# PaxInstrument-T400D.net
KiCad netlist of a schematic drawn in EAGLE
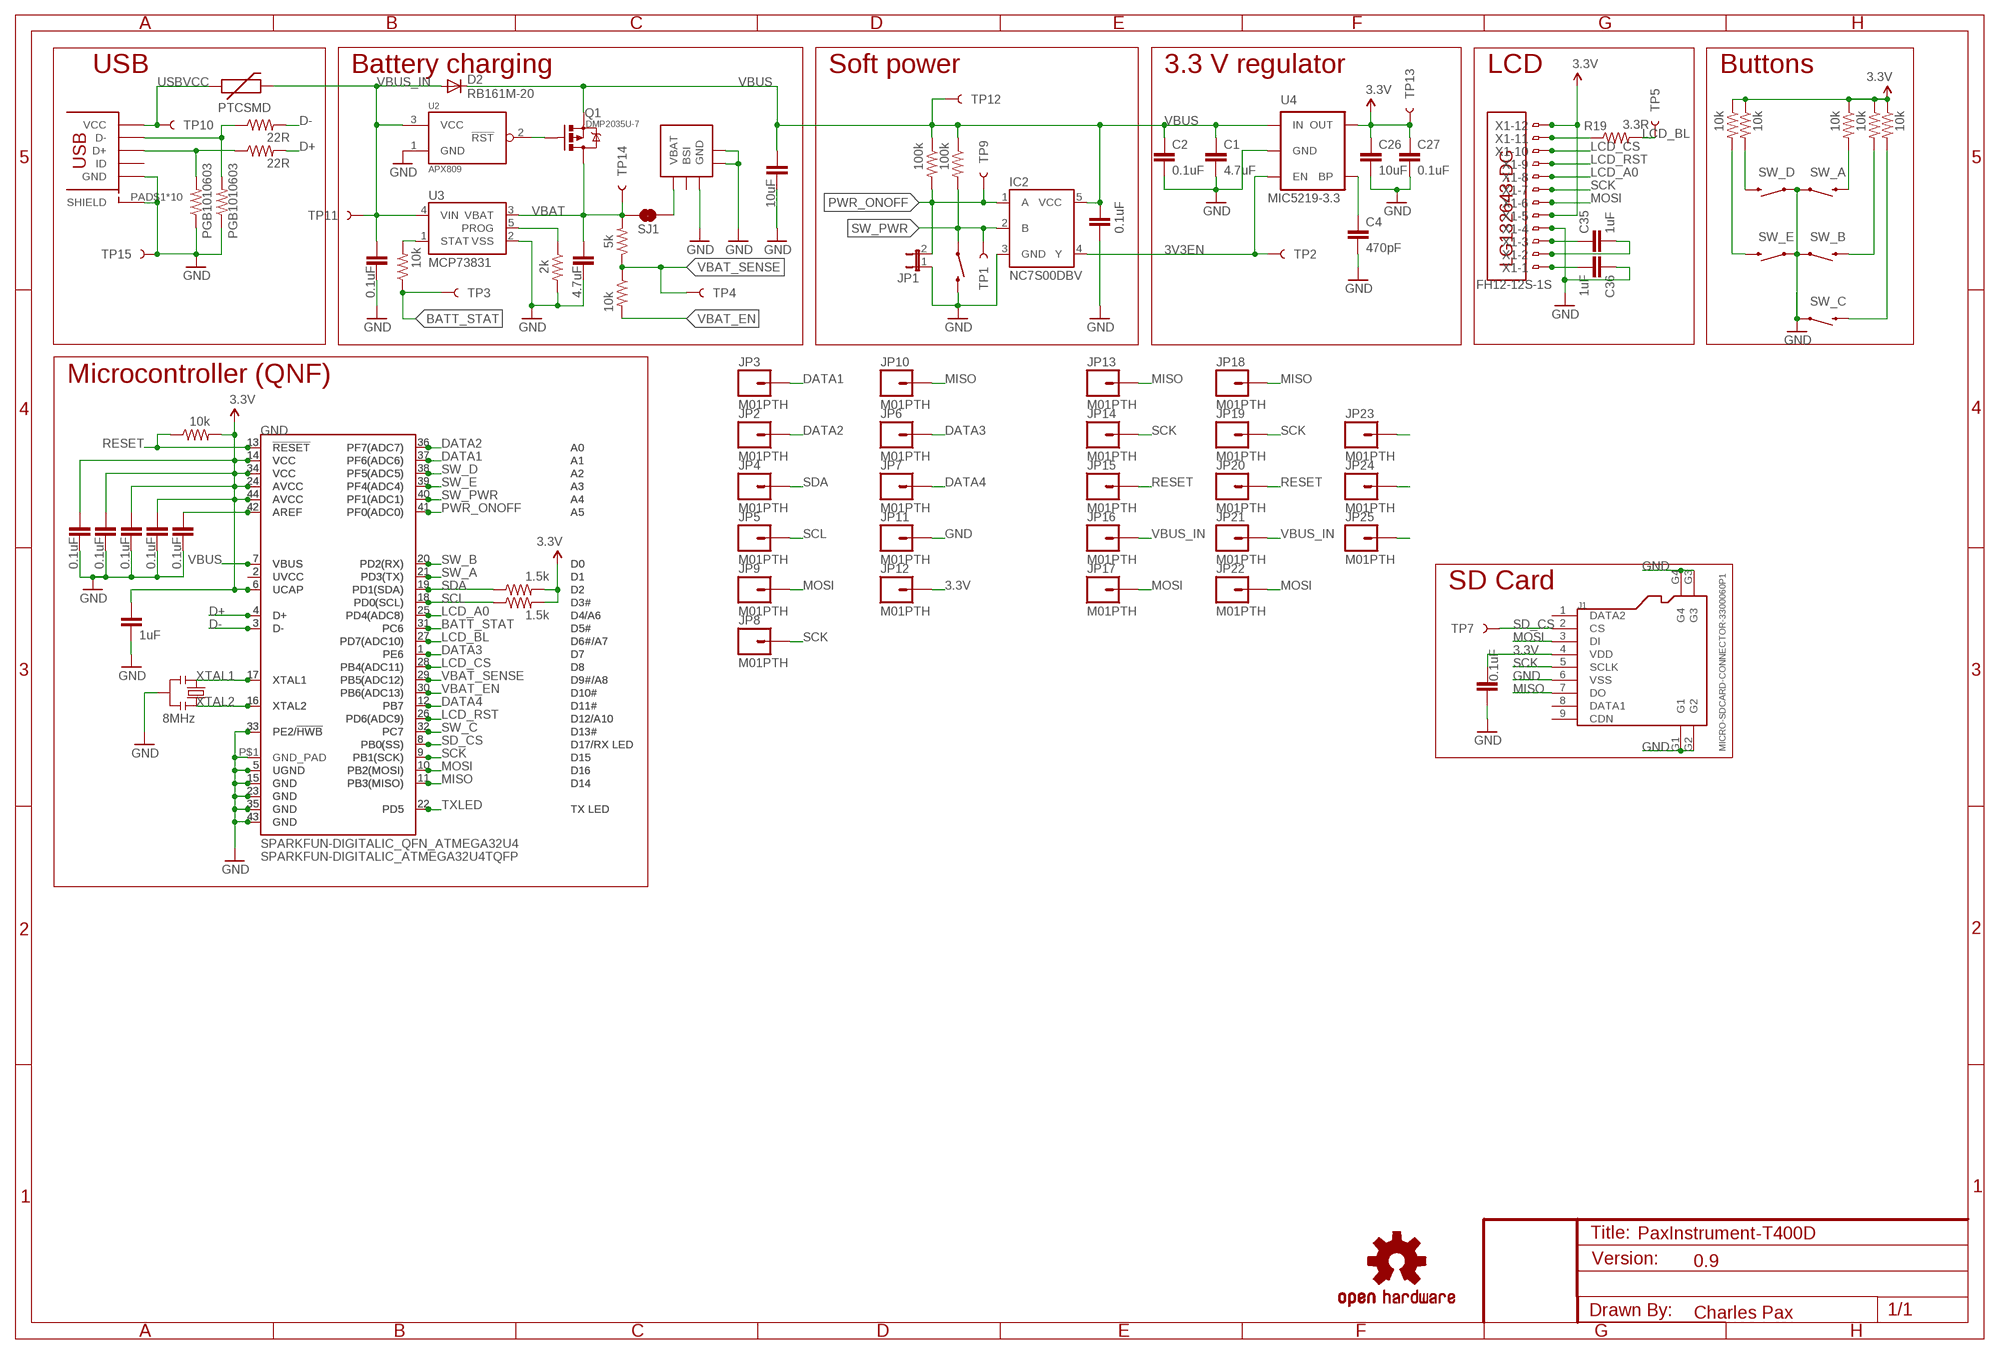
[diagram p0: schematic, sheet 1]

(export (version "E")
  (design (tool "Eeschema 10.0.6"))
  (components
    (comp (ref "C1")
      (value "4.7uF")
      (footprint "eagle-import:SPARKFUN-CAPACITORS_0603-CAP")
      (fields (field (name "MPN") "GRM188R60J475KE19D"))
      (libsource (lib "eagle-import") (part "SPARKFUN-CAPACITORS_CAP0603-CAP"))
    )
    (comp (ref "C2")
      (value "0.1uF")
      (footprint "eagle-import:SPARKFUN-CAPACITORS_0603-CAP")
      (fields (field (name "MPN") "CL10B104KO8NNNC"))
      (libsource (lib "eagle-import") (part "SPARKFUN-CAPACITORS_CAP0603-CAP"))
    )
    (comp (ref "C3")
      (value "0.1uF")
      (footprint "eagle-import:SPARKFUN-CAPACITORS_0603-CAP")
      (fields (field (name "MPN") "CL10B104KO8NNNC"))
      (libsource (lib "eagle-import") (part "SPARKFUN-CAPACITORS_CAP0603-CAP"))
    )
    (comp (ref "C4")
      (value "470pF")
      (footprint "eagle-import:SPARKFUN-CAPACITORS_0603-CAP")
      (fields (field (name "MPN") "C1608X5R1A474K080AA"))
      (libsource (lib "eagle-import") (part "SPARKFUN-CAPACITORS_CAP0603-CAP"))
    )
    (comp (ref "C5")
      (value "0.1uF")
      (footprint "eagle-import:SPARKFUN-CAPACITORS_0603-CAP")
      (fields (field (name "MPN") "CL10B104KO8NNNC"))
      (libsource (lib "eagle-import") (part "SPARKFUN-CAPACITORS_CAP0603-CAP"))
    )
    (comp (ref "C6")
      (value "0.1uF")
      (footprint "eagle-import:SPARKFUN-CAPACITORS_0603-CAP")
      (fields (field (name "MPN") "CL10B104KO8NNNC"))
      (libsource (lib "eagle-import") (part "SPARKFUN-CAPACITORS_CAP0603-CAP"))
    )
    (comp (ref "C9")
      (value "4.7uF")
      (footprint "eagle-import:SPARKFUN-CAPACITORS_0603-CAP")
      (fields (field (name "MPN") "GRM188R60J475KE19D"))
      (libsource (lib "eagle-import") (part "SPARKFUN-CAPACITORS_CAP0603-CAP"))
    )
    (comp (ref "C12")
      (value "10uF")
      (footprint "eagle-import:SPARKFUN-CAPACITORS_0603-CAP")
      (fields (field (name "MPN") "JMK107ABJ106MAHT"))
      (libsource (lib "eagle-import") (part "SPARKFUN-CAPACITORS_CAP0603-CAP"))
    )
    (comp (ref "C19")
      (value "1uF")
      (footprint "eagle-import:SPARKFUN-CAPACITORS_0603-CAP")
      (fields (field (name "MPN") "LMK107B7105KA-T"))
      (libsource (lib "eagle-import") (part "SPARKFUN-CAPACITORS_CAP0603-CAP"))
    )
    (comp (ref "C21")
      (value "0.1uF")
      (footprint "eagle-import:SPARKFUN-CAPACITORS_0603-CAP")
      (fields (field (name "MPN") "CL10B104KO8NNNC"))
      (libsource (lib "eagle-import") (part "SPARKFUN-CAPACITORS_CAP0603-CAP"))
    )
    (comp (ref "C26")
      (value "10uF")
      (footprint "eagle-import:SPARKFUN-CAPACITORS_0603-CAP")
      (fields (field (name "MPN") "JMK107ABJ106MAHT"))
      (libsource (lib "eagle-import") (part "SPARKFUN-CAPACITORS_CAP0603-CAP"))
    )
    (comp (ref "C27")
      (value "0.1uF")
      (footprint "eagle-import:SPARKFUN-CAPACITORS_0603-CAP")
      (fields (field (name "MPN") "CL10B104KO8NNNC"))
      (libsource (lib "eagle-import") (part "SPARKFUN-CAPACITORS_CAP0603-CAP"))
    )
    (comp (ref "C28")
      (value "0.1uF")
      (footprint "eagle-import:SPARKFUN-CAPACITORS_0603-CAP")
      (fields (field (name "MPN") "CL10B104KO8NNNC"))
      (libsource (lib "eagle-import") (part "SPARKFUN-CAPACITORS_CAP0603-CAP"))
    )
    (comp (ref "C32")
      (value "0.1uF")
      (footprint "eagle-import:SPARKFUN-CAPACITORS_0603-CAP")
      (fields (field (name "MPN") "CL10B104KO8NNNC"))
      (libsource (lib "eagle-import") (part "SPARKFUN-CAPACITORS_CAP0603-CAP"))
    )
    (comp (ref "C33")
      (value "0.1uF")
      (footprint "eagle-import:SPARKFUN-CAPACITORS_0603-CAP")
      (fields (field (name "MPN") "CL10B104KO8NNNC"))
      (libsource (lib "eagle-import") (part "SPARKFUN-CAPACITORS_CAP0603-CAP"))
    )
    (comp (ref "C34")
      (value "0.1uF")
      (footprint "eagle-import:SPARKFUN-CAPACITORS_0603-CAP")
      (fields (field (name "MPN") "CL10B104KO8NNNC"))
      (libsource (lib "eagle-import") (part "SPARKFUN-CAPACITORS_CAP0603-CAP"))
    )
    (comp (ref "C35")
      (value "1uF")
      (footprint "eagle-import:SPARKFUN-CAPACITORS_0603-CAP")
      (fields (field (name "MPN") "LMK107B7105KA-T"))
      (libsource (lib "eagle-import") (part "SPARKFUN-CAPACITORS_CAP0603-CAP"))
    )
    (comp (ref "C36")
      (value "1uF")
      (footprint "eagle-import:SPARKFUN-CAPACITORS_0603-CAP")
      (fields (field (name "MPN") "LMK107B7105KA-T"))
      (libsource (lib "eagle-import") (part "SPARKFUN-CAPACITORS_CAP0603-CAP"))
    )
    (comp (ref "D2")
      (value "RB161M-20")
      (footprint "eagle-import:SOD123")
      (fields (field (name "MPN") "B340A-13-F"))
      (libsource (lib "eagle-import") (part "SPARKFUN-DISCRETESEMI_DIODESOD123SOD123"))
    )
    (comp (ref "F1")
      (value "PTCSMD")
      (footprint "eagle-import:PTC-1206")
      (fields (field (name "MPN") "MF-NSMF050-2"))
      (libsource (lib "eagle-import") (part "PTCSMD"))
    )
    (comp (ref "GND")
      (value "SPARKFUN-DIGITALIC_QFN_ATMEGA32U4")
      (footprint "eagle-import:SPARKFUN-DIGITALIC_SPARKFUN-DIGITALIC_QFN-44")
      (libsource (lib "eagle-import") (part "SPARKFUN-DIGITALIC_QFN_ATMEGA32U4"))
    )
    (comp (ref "IC2")
      (value "NC7S00DBV")
      (footprint "eagle-import:CHARLESPAX_SOT23-5")
      (libsource (lib "eagle-import") (part "NC7S00DBV"))
    )
    (comp (ref "J1")
      (value "MICRO-SDCARD-CONNECTOR-3300060P1")
      (footprint "eagle-import:9P-SMD-W-RING")
      (libsource (lib "eagle-import") (part "MICRO-SDCARD-CONNECTOR-3300060P1"))
    )
    (comp (ref "JP1")
      (value "JUMPER-2SMD-NO")
      (footprint "eagle-import:SJ_2S-NO")
      (libsource (lib "eagle-import") (part "JUMPER-2SMD-NO"))
    )
    (comp (ref "JP2")
      (value "M01PTH")
      (footprint "eagle-import:1X01")
      (libsource (lib "eagle-import") (part "M01PTH"))
    )
    (comp (ref "JP3")
      (value "M01PTH")
      (footprint "eagle-import:1X01")
      (libsource (lib "eagle-import") (part "M01PTH"))
    )
    (comp (ref "JP4")
      (value "M01PTH")
      (footprint "eagle-import:1X01")
      (libsource (lib "eagle-import") (part "M01PTH"))
    )
    (comp (ref "JP5")
      (value "M01PTH")
      (footprint "eagle-import:1X01")
      (libsource (lib "eagle-import") (part "M01PTH"))
    )
    (comp (ref "JP6")
      (value "M01PTH")
      (footprint "eagle-import:1X01")
      (libsource (lib "eagle-import") (part "M01PTH"))
    )
    (comp (ref "JP7")
      (value "M01PTH")
      (footprint "eagle-import:1X01")
      (libsource (lib "eagle-import") (part "M01PTH"))
    )
    (comp (ref "JP8")
      (value "M01PTH")
      (footprint "eagle-import:1X01")
      (libsource (lib "eagle-import") (part "M01PTH"))
    )
    (comp (ref "JP9")
      (value "M01PTH")
      (footprint "eagle-import:1X01")
      (libsource (lib "eagle-import") (part "M01PTH"))
    )
    (comp (ref "JP10")
      (value "M01PTH")
      (footprint "eagle-import:1X01")
      (libsource (lib "eagle-import") (part "M01PTH"))
    )
    (comp (ref "JP11")
      (value "M01PTH")
      (footprint "eagle-import:1X01")
      (libsource (lib "eagle-import") (part "M01PTH"))
    )
    (comp (ref "JP12")
      (value "M01PTH")
      (footprint "eagle-import:1X01")
      (libsource (lib "eagle-import") (part "M01PTH"))
    )
    (comp (ref "JP13")
      (value "M01PTH")
      (footprint "eagle-import:1X01")
      (libsource (lib "eagle-import") (part "M01PTH"))
    )
    (comp (ref "JP14")
      (value "M01PTH")
      (footprint "eagle-import:1X01")
      (libsource (lib "eagle-import") (part "M01PTH"))
    )
    (comp (ref "JP15")
      (value "M01PTH")
      (footprint "eagle-import:1X01")
      (libsource (lib "eagle-import") (part "M01PTH"))
    )
    (comp (ref "JP16")
      (value "M01PTH")
      (footprint "eagle-import:1X01")
      (libsource (lib "eagle-import") (part "M01PTH"))
    )
    (comp (ref "JP17")
      (value "M01PTH")
      (footprint "eagle-import:1X01")
      (libsource (lib "eagle-import") (part "M01PTH"))
    )
    (comp (ref "JP18")
      (value "M01PTH")
      (footprint "eagle-import:1X01")
      (libsource (lib "eagle-import") (part "M01PTH"))
    )
    (comp (ref "JP19")
      (value "M01PTH")
      (footprint "eagle-import:1X01")
      (libsource (lib "eagle-import") (part "M01PTH"))
    )
    (comp (ref "JP20")
      (value "M01PTH")
      (footprint "eagle-import:1X01")
      (libsource (lib "eagle-import") (part "M01PTH"))
    )
    (comp (ref "JP21")
      (value "M01PTH")
      (footprint "eagle-import:1X01")
      (libsource (lib "eagle-import") (part "M01PTH"))
    )
    (comp (ref "JP22")
      (value "M01PTH")
      (footprint "eagle-import:1X01")
      (libsource (lib "eagle-import") (part "M01PTH"))
    )
    (comp (ref "JP23")
      (value "M01PTH")
      (footprint "eagle-import:1X01")
      (libsource (lib "eagle-import") (part "M01PTH"))
    )
    (comp (ref "JP24")
      (value "M01PTH")
      (footprint "eagle-import:1X01")
      (libsource (lib "eagle-import") (part "M01PTH"))
    )
    (comp (ref "JP25")
      (value "M01PTH")
      (footprint "eagle-import:1X01")
      (libsource (lib "eagle-import") (part "M01PTH"))
    )
    (comp (ref "LOGO1")
      (value "OSHW-LOGOS")
      (footprint "eagle-import:OSHW-LOGO-S")
      (libsource (lib "eagle-import") (part "OSHW-LOGOS"))
    )
    (comp (ref "Q1")
      (value "DMP2035U-7")
      (footprint "eagle-import:SOT23")
      (libsource (lib "eagle-import") (part "MOSFET-PCHANNELSMT"))
    )
    (comp (ref "R3")
      (value "2k")
      (footprint "eagle-import:SPARKFUN-RESISTORS_0603-RES")
      (fields (field (name "MPN") "ESR03EZPJ202"))
      (libsource (lib "eagle-import") (part "SPARKFUN-RESISTORS_RESISTOR0603-RES"))
    )
    (comp (ref "R4")
      (value "10k")
      (footprint "eagle-import:SPARKFUN-RESISTORS_0603-RES")
      (fields (field (name "MPN") "RC1608J103CS"))
      (libsource (lib "eagle-import") (part "SPARKFUN-RESISTORS_RESISTOR0603-RES"))
    )
    (comp (ref "R6")
      (value "100k")
      (footprint "eagle-import:SPARKFUN-RESISTORS_0603-RES")
      (fields (field (name "MPN") "RC1608J103CS"))
      (libsource (lib "eagle-import") (part "SPARKFUN-RESISTORS_RESISTOR0603-RES"))
    )
    (comp (ref "R7")
      (value "100k")
      (footprint "eagle-import:SPARKFUN-RESISTORS_0603-RES")
      (fields (field (name "MPN") "RC1608J103CS"))
      (libsource (lib "eagle-import") (part "SPARKFUN-RESISTORS_RESISTOR0603-RES"))
    )
    (comp (ref "R8")
      (value "10k")
      (footprint "eagle-import:SPARKFUN-RESISTORS_0603-RES")
      (fields (field (name "MPN") "RC1608J103CS"))
      (libsource (lib "eagle-import") (part "SPARKFUN-RESISTORS_RESISTOR0603-RES"))
    )
    (comp (ref "R9")
      (value "22R")
      (footprint "eagle-import:SPARKFUN-RESISTORS_0603-RES")
      (fields (field (name "MPN") "RC0603JR-0722RL"))
      (libsource (lib "eagle-import") (part "SPARKFUN-RESISTORS_RESISTOR0603-RES"))
    )
    (comp (ref "R10")
      (value "22R")
      (footprint "eagle-import:SPARKFUN-RESISTORS_0603-RES")
      (fields (field (name "MPN") "RC0603JR-0722RL"))
      (libsource (lib "eagle-import") (part "SPARKFUN-RESISTORS_RESISTOR0603-RES"))
    )
    (comp (ref "R11")
      (value "10k")
      (footprint "eagle-import:SPARKFUN-RESISTORS_0603-RES")
      (fields (field (name "MPN") "RC1608J103CS"))
      (libsource (lib "eagle-import") (part "SPARKFUN-RESISTORS_RESISTOR0603-RES"))
    )
    (comp (ref "R12")
      (value "10k")
      (footprint "eagle-import:SPARKFUN-RESISTORS_0603-RES")
      (fields (field (name "MPN") "RC1608J103CS"))
      (libsource (lib "eagle-import") (part "SPARKFUN-RESISTORS_RESISTOR0603-RES"))
    )
    (comp (ref "R13")
      (value "1.5k")
      (footprint "eagle-import:SPARKFUN-RESISTORS_0603-RES")
      (fields (field (name "MPN") "RC0603JR-071K5L"))
      (libsource (lib "eagle-import") (part "SPARKFUN-RESISTORS_RESISTOR0603-RES"))
    )
    (comp (ref "R14")
      (value "1.5k")
      (footprint "eagle-import:SPARKFUN-RESISTORS_0603-RES")
      (fields (field (name "MPN") "RC0603JR-071K5L"))
      (libsource (lib "eagle-import") (part "SPARKFUN-RESISTORS_RESISTOR0603-RES"))
    )
    (comp (ref "R15")
      (value "10k")
      (footprint "eagle-import:SPARKFUN-RESISTORS_0603-RES")
      (fields (field (name "MPN") "RC1608J103CS"))
      (libsource (lib "eagle-import") (part "SPARKFUN-RESISTORS_RESISTOR0603-RES"))
    )
    (comp (ref "R16")
      (value "10k")
      (footprint "eagle-import:SPARKFUN-RESISTORS_0603-RES")
      (fields (field (name "MPN") "RC1608J103CS"))
      (libsource (lib "eagle-import") (part "SPARKFUN-RESISTORS_RESISTOR0603-RES"))
    )
    (comp (ref "R17")
      (value "10k")
      (footprint "eagle-import:SPARKFUN-RESISTORS_0603-RES")
      (fields (field (name "MPN") "RC1608J103CS"))
      (libsource (lib "eagle-import") (part "SPARKFUN-RESISTORS_RESISTOR0603-RES"))
    )
    (comp (ref "R19")
      (value "3.3R")
      (footprint "eagle-import:SPARKFUN-RESISTORS_0603-RES")
      (libsource (lib "eagle-import") (part "SPARKFUN-RESISTORS_RESISTOR0603-RES"))
    )
    (comp (ref "R20")
      (value "5k")
      (footprint "eagle-import:SPARKFUN-RESISTORS_0603-RES")
      (fields (field (name "MPN") "RC1608J103CS"))
      (libsource (lib "eagle-import") (part "SPARKFUN-RESISTORS_RESISTOR0603-RES"))
    )
    (comp (ref "R24")
      (value "10k")
      (footprint "eagle-import:SPARKFUN-RESISTORS_0603-RES")
      (fields (field (name "MPN") "RC1608J103CS"))
      (libsource (lib "eagle-import") (part "SPARKFUN-RESISTORS_RESISTOR0603-RES"))
    )
    (comp (ref "S1")
      (value "SWITCH-MOMENTARY-2SMD")
      (footprint "eagle-import:TACTILE_SWITCH_SMD")
      (libsource (lib "eagle-import") (part "SWITCH-MOMENTARY-2SMD"))
    )
    (comp (ref "S2")
      (value "SWITCH-MOMENTARY-2SMD")
      (footprint "eagle-import:TACTILE_SWITCH_SMD")
      (libsource (lib "eagle-import") (part "SWITCH-MOMENTARY-2SMD"))
    )
    (comp (ref "S3")
      (value "SWITCH-MOMENTARY-2SMD")
      (footprint "eagle-import:TACTILE_SWITCH_SMD")
      (libsource (lib "eagle-import") (part "SWITCH-MOMENTARY-2SMD"))
    )
    (comp (ref "S4")
      (value "SWITCH-MOMENTARY-2SMD")
      (footprint "eagle-import:TACTILE_SWITCH_SMD")
      (libsource (lib "eagle-import") (part "SWITCH-MOMENTARY-2SMD"))
    )
    (comp (ref "S5")
      (value "SWITCH-MOMENTARY-2SMD")
      (footprint "eagle-import:TACTILE_SWITCH_SMD")
      (libsource (lib "eagle-import") (part "SWITCH-MOMENTARY-2SMD"))
    )
    (comp (ref "S6")
      (value "SWITCH-MOMENTARY-2SMD")
      (footprint "eagle-import:TACTILE_SWITCH_SMD")
      (libsource (lib "eagle-import") (part "SWITCH-MOMENTARY-2SMD"))
    )
    (comp (ref "SJ1")
      (value "JUMPER-PAD-2-NC_BY_TRACE")
      (footprint "eagle-import:PAD-JUMPER-2-NC_BY_TRACE_YES_SILK")
      (libsource (lib "eagle-import") (part "JUMPER-PAD-2-NC_BY_TRACE"))
    )
    (comp (ref "TP1")
      (value "SW_PWR")
      (footprint "eagle-import:TP_15TH")
      (libsource (lib "eagle-import") (part "TEST-POINTTP_15TH_THRU"))
    )
    (comp (ref "TP2")
      (value "3V3_EN")
      (footprint "eagle-import:TP_15TH")
      (libsource (lib "eagle-import") (part "TEST-POINTTP_15TH_THRU"))
    )
    (comp (ref "TP3")
      (value "BATT_STAT")
      (footprint "eagle-import:TP_15TH")
      (libsource (lib "eagle-import") (part "TEST-POINTTP_15TH_THRU"))
    )
    (comp (ref "TP4")
      (value "VBAT_SENSE")
      (footprint "eagle-import:TP_15TH")
      (libsource (lib "eagle-import") (part "TEST-POINTTP_15TH_THRU"))
    )
    (comp (ref "TP5")
      (value "LCD_BL")
      (footprint "eagle-import:TP_15TH")
      (libsource (lib "eagle-import") (part "TEST-POINTTP_15TH_THRU"))
    )
    (comp (ref "TP7")
      (value "SD_CS")
      (footprint "eagle-import:TP_15TH")
      (libsource (lib "eagle-import") (part "TEST-POINTTP_15TH_THRU"))
    )
    (comp (ref "TP9")
      (value "PWR_ON/OFF")
      (footprint "eagle-import:TP_15TH")
      (libsource (lib "eagle-import") (part "TEST-POINTTP_15TH_THRU"))
    )
    (comp (ref "TP10")
      (value "TEST-POINTTP_15TH_THRU")
      (footprint "eagle-import:TP_15TH")
      (libsource (lib "eagle-import") (part "TEST-POINTTP_15TH_THRU"))
    )
    (comp (ref "TP11")
      (value "VBUS_IN")
      (footprint "eagle-import:TP_15TH")
      (libsource (lib "eagle-import") (part "TEST-POINTTP_15TH_THRU"))
    )
    (comp (ref "TP12")
      (value "VBUS")
      (footprint "eagle-import:TP_15TH")
      (libsource (lib "eagle-import") (part "TEST-POINTTP_15TH_THRU"))
    )
    (comp (ref "TP13")
      (value "3.3V")
      (footprint "eagle-import:TP_15TH")
      (libsource (lib "eagle-import") (part "TEST-POINTTP_15TH_THRU"))
    )
    (comp (ref "TP14")
      (value "VBAT")
      (footprint "eagle-import:TP_15TH")
      (libsource (lib "eagle-import") (part "TEST-POINTTP_15TH_THRU"))
    )
    (comp (ref "TP15")
      (value "GND")
      (footprint "eagle-import:TP_15TH")
      (libsource (lib "eagle-import") (part "TEST-POINTTP_15TH_THRU"))
    )
    (comp (ref "U$1")
      (value "USB_MICROSMT+THRUHULE")
      (footprint "eagle-import:USB_MICRO_THRUHOLE")
      (fields (field (name "MPN") "10118194-0001LF"))
      (libsource (lib "eagle-import") (part "USB_MICROSMT+THRUHULE"))
    )
    (comp (ref "U$2")
      (value "BL-5C-CONNECTOR")
      (footprint "eagle-import:BL-5C-CONNECTOR")
      (libsource (lib "eagle-import") (part "BL-5C-CONNECTOR"))
    )
    (comp (ref "U$3")
      (value "SPARKFUN-DIGITALIC_ATMEGA32U4TQFP")
      (footprint "eagle-import:SPARKFUN-DIGITALIC_SPARKFUN-DIGITALIC_TQFP44")
      (libsource (lib "eagle-import") (part "SPARKFUN-DIGITALIC_ATMEGA32U4TQFP"))
    )
    (comp (ref "U$5")
      (value "LG132643-DG")
      (footprint "eagle-import:LG132643-DG")
      (fields (field (name "MPN") "LG132643-DW"))
      (libsource (lib "eagle-import") (part "LG132643-DG"))
    )
    (comp (ref "U2")
      (value "APX809")
      (footprint "eagle-import:SOT23")
      (libsource (lib "eagle-import") (part "APX809"))
    )
    (comp (ref "U3")
      (value "MCP73831")
      (footprint "eagle-import:SOT23-5")
      (fields (field (name "MPN") "MCP73831T-2DCI/OT"))
      (libsource (lib "eagle-import") (part "MCP73831"))
    )
    (comp (ref "U4")
      (value "MIC5219-3.3V")
      (footprint "eagle-import:SOT23-5")
      (fields (field (name "MPN") "MIC5219-3.3YM5 TR"))
      (libsource (lib "eagle-import") (part "V_REG_LDOSMD"))
    )
    (comp (ref "X1")
      (value "FH12-12S-1S")
      (footprint "eagle-import:FH12-12S-1SH")
      (libsource (lib "eagle-import") (part "FH12-12S-1S"))
    )
    (comp (ref "X2")
      (value "FH12-12S-0.5SH")
      (footprint "eagle-import:FH12-12S-0.5SH")
      (fields (field (name "MPN") "FH12-12S-0.5SH(55)"))
      (libsource (lib "eagle-import") (part "FH12-12S-0.5SH"))
    )
    (comp (ref "Y1")
      (value "RESONATORSMD")
      (footprint "eagle-import:RESONATOR-SMD")
      (fields (field (name "MPN") "CSTCE8M00G52-R0"))
      (libsource (lib "eagle-import") (part "RESONATORSMD"))
    )
    (comp (ref "Z1")
      (value "PGB1010603")
      (footprint "eagle-import:SPARKFUN-RESISTORS_0603-RES")
      (fields (field (name "MPN") "PGB1010603NRHF"))
      (libsource (lib "eagle-import") (part "SPARKFUN-RESISTORS_RESISTOR0603-RES"))
    )
    (comp (ref "Z2")
      (value "PGB1010603")
      (footprint "eagle-import:SPARKFUN-RESISTORS_0603-RES")
      (fields (field (name "MPN") "PGB1010603NRHF"))
      (libsource (lib "eagle-import") (part "SPARKFUN-RESISTORS_RESISTOR0603-RES"))
    )
  )
  (nets
    (net (code "1") (name "/3V3EN") (class "Default")
      (node (ref "IC2") (pin "4") (pinfunction "Y_4") (pintype "output"))
      (node (ref "TP2") (pin "P$1") (pinfunction "1_P$1") (pintype "bidirectional"))
      (node (ref "U4") (pin "3") (pinfunction "EN_3") (pintype "input"))
    )
    (net (code "2") (name "/D+") (class "Default")
      (node (ref "GND") (pin "4") (pinfunction "D+_4") (pintype "bidirectional"))
      (node (ref "R9") (pin "2") (pinfunction "2_2") (pintype "passive"))
      (node (ref "U$3") (pin "4") (pinfunction "D+_4") (pintype "bidirectional"))
    )
    (net (code "3") (name "/D-") (class "Default")
      (node (ref "GND") (pin "3") (pinfunction "D-_3") (pintype "bidirectional"))
      (node (ref "R10") (pin "2") (pinfunction "2_2") (pintype "passive"))
      (node (ref "U$3") (pin "3") (pinfunction "D-_3") (pintype "bidirectional"))
    )
    (net (code "4") (name "/DATA1") (class "Default")
      (node (ref "GND") (pin "37") (pinfunction "PF6(ADC6)_37") (pintype "bidirectional"))
      (node (ref "JP3") (pin "1") (pinfunction "1_1") (pintype "passive"))
      (node (ref "U$3") (pin "37") (pinfunction "PF6(ADC6)_37") (pintype "bidirectional"))
    )
    (net (code "5") (name "/DATA2") (class "Default")
      (node (ref "GND") (pin "36") (pinfunction "PF7(ADC7)_36") (pintype "bidirectional"))
      (node (ref "JP2") (pin "1") (pinfunction "1_1") (pintype "passive"))
      (node (ref "U$3") (pin "36") (pinfunction "PF7(ADC7)_36") (pintype "bidirectional"))
    )
    (net (code "6") (name "/DATA3") (class "Default")
      (node (ref "GND") (pin "1") (pinfunction "PE6_1") (pintype "bidirectional"))
      (node (ref "JP6") (pin "1") (pinfunction "1_1") (pintype "passive"))
      (node (ref "U$3") (pin "1") (pinfunction "PE6_1") (pintype "bidirectional"))
    )
    (net (code "7") (name "/DATA4") (class "Default")
      (node (ref "GND") (pin "12") (pinfunction "PB7_12") (pintype "bidirectional"))
      (node (ref "JP7") (pin "1") (pinfunction "1_1") (pintype "passive"))
      (node (ref "U$3") (pin "12") (pinfunction "PB7_12") (pintype "bidirectional"))
    )
    (net (code "8") (name "/LCD_A0") (class "Default")
      (node (ref "GND") (pin "25") (pinfunction "PD4(ADC8)_25") (pintype "bidirectional"))
      (node (ref "U$3") (pin "25") (pinfunction "PD4(ADC8)_25") (pintype "bidirectional"))
      (node (ref "X1") (pin "8") (pinfunction "1_8") (pintype "passive"))
      (node (ref "X2") (pin "8") (pinfunction "1_8") (pintype "passive"))
    )
    (net (code "9") (name "/LCD_BL") (class "Default")
      (node (ref "GND") (pin "27") (pinfunction "PD7(ADC10)_27") (pintype "bidirectional"))
      (node (ref "R19") (pin "2") (pinfunction "2_2") (pintype "passive"))
      (node (ref "TP5") (pin "P$1") (pinfunction "1_P$1") (pintype "bidirectional"))
      (node (ref "U$3") (pin "27") (pinfunction "PD7(ADC10)_27") (pintype "bidirectional"))
    )
    (net (code "10") (name "/LCD_CS") (class "Default")
      (node (ref "GND") (pin "28") (pinfunction "PB4(ADC11)_28") (pintype "bidirectional"))
      (node (ref "U$3") (pin "28") (pinfunction "PB4(ADC11)_28") (pintype "bidirectional"))
      (node (ref "X1") (pin "10") (pinfunction "1_10") (pintype "passive"))
      (node (ref "X2") (pin "10") (pinfunction "1_10") (pintype "passive"))
    )
    (net (code "11") (name "/LCD_RST") (class "Default")
      (node (ref "GND") (pin "26") (pinfunction "PD6(ADC9)_26") (pintype "bidirectional"))
      (node (ref "U$3") (pin "26") (pinfunction "PD6(ADC9)_26") (pintype "bidirectional"))
      (node (ref "X1") (pin "9") (pinfunction "1_9") (pintype "passive"))
      (node (ref "X2") (pin "9") (pinfunction "1_9") (pintype "passive"))
    )
    (net (code "12") (name "/MISO") (class "Default")
      (node (ref "GND") (pin "11") (pinfunction "PB3(MISO)_11") (pintype "bidirectional"))
      (node (ref "J1") (pin "7") (pinfunction "DO_7") (pintype "bidirectional"))
      (node (ref "JP10") (pin "1") (pinfunction "1_1") (pintype "passive"))
      (node (ref "JP13") (pin "1") (pinfunction "1_1") (pintype "passive"))
      (node (ref "JP18") (pin "1") (pinfunction "1_1") (pintype "passive"))
      (node (ref "U$3") (pin "11") (pinfunction "PB3(MISO)_11") (pintype "bidirectional"))
    )
    (net (code "13") (name "/MOSI") (class "Default")
      (node (ref "GND") (pin "10") (pinfunction "PB2(MOSI)_10") (pintype "bidirectional"))
      (node (ref "J1") (pin "3") (pinfunction "DI_3") (pintype "bidirectional"))
      (node (ref "JP17") (pin "1") (pinfunction "1_1") (pintype "passive"))
      (node (ref "JP22") (pin "1") (pinfunction "1_1") (pintype "passive"))
      (node (ref "JP9") (pin "1") (pinfunction "1_1") (pintype "passive"))
      (node (ref "U$3") (pin "10") (pinfunction "PB2(MOSI)_10") (pintype "bidirectional"))
      (node (ref "X1") (pin "6") (pinfunction "1_6") (pintype "passive"))
      (node (ref "X2") (pin "6") (pinfunction "1_6") (pintype "passive"))
    )
    (net (code "14") (name "/RESET") (class "Default")
      (node (ref "GND") (pin "13") (pinfunction "~{RESET}_13") (pintype "bidirectional"))
      (node (ref "JP15") (pin "1") (pinfunction "1_1") (pintype "passive"))
      (node (ref "JP20") (pin "1") (pinfunction "1_1") (pintype "passive"))
      (node (ref "R4") (pin "1") (pinfunction "1_1") (pintype "passive"))
      (node (ref "U$3") (pin "13") (pinfunction "~{RESET}_13") (pintype "bidirectional"))
    )
    (net (code "15") (name "/SCK") (class "Default")
      (node (ref "GND") (pin "9") (pinfunction "PB1(SCK)_9") (pintype "bidirectional"))
      (node (ref "J1") (pin "5") (pinfunction "SCLK_5") (pintype "bidirectional"))
      (node (ref "JP14") (pin "1") (pinfunction "1_1") (pintype "passive"))
      (node (ref "JP19") (pin "1") (pinfunction "1_1") (pintype "passive"))
      (node (ref "JP8") (pin "1") (pinfunction "1_1") (pintype "passive"))
      (node (ref "U$3") (pin "9") (pinfunction "PB1(SCK)_9") (pintype "bidirectional"))
      (node (ref "X1") (pin "7") (pinfunction "1_7") (pintype "passive"))
      (node (ref "X2") (pin "7") (pinfunction "1_7") (pintype "passive"))
    )
    (net (code "16") (name "/SCL") (class "Default")
      (node (ref "GND") (pin "18") (pinfunction "PD0(SCL)_18") (pintype "bidirectional"))
      (node (ref "JP5") (pin "1") (pinfunction "1_1") (pintype "passive"))
      (node (ref "R14") (pin "1") (pinfunction "1_1") (pintype "passive"))
      (node (ref "U$3") (pin "18") (pinfunction "PD0(SCL)_18") (pintype "bidirectional"))
    )
    (net (code "17") (name "/SDA") (class "Default")
      (node (ref "GND") (pin "19") (pinfunction "PD1(SDA)_19") (pintype "bidirectional"))
      (node (ref "JP4") (pin "1") (pinfunction "1_1") (pintype "passive"))
      (node (ref "R13") (pin "1") (pinfunction "1_1") (pintype "passive"))
      (node (ref "U$3") (pin "19") (pinfunction "PD1(SDA)_19") (pintype "bidirectional"))
    )
    (net (code "18") (name "/SD_CS") (class "Default")
      (node (ref "GND") (pin "8") (pinfunction "PB0(SS)_8") (pintype "bidirectional"))
      (node (ref "J1") (pin "2") (pinfunction "CS_2") (pintype "bidirectional"))
      (node (ref "TP7") (pin "P$1") (pinfunction "1_P$1") (pintype "bidirectional"))
      (node (ref "U$3") (pin "8") (pinfunction "PB0(SS)_8") (pintype "bidirectional"))
    )
    (net (code "19") (name "/SW_A") (class "Default")
      (node (ref "GND") (pin "21") (pinfunction "PD3(TX)_21") (pintype "bidirectional"))
      (node (ref "R8") (pin "2") (pinfunction "2_2") (pintype "passive"))
      (node (ref "S3") (pin "3") (pinfunction "2_3") (pintype "passive"))
      (node (ref "U$3") (pin "21") (pinfunction "PD3(TX)_21") (pintype "bidirectional"))
    )
    (net (code "20") (name "/SW_B") (class "Default")
      (node (ref "GND") (pin "20") (pinfunction "PD2(RX)_20") (pintype "bidirectional"))
      (node (ref "R11") (pin "2") (pinfunction "2_2") (pintype "passive"))
      (node (ref "S2") (pin "3") (pinfunction "2_3") (pintype "passive"))
      (node (ref "U$3") (pin "20") (pinfunction "PD2(RX)_20") (pintype "bidirectional"))
    )
    (net (code "21") (name "/SW_C") (class "Default")
      (node (ref "GND") (pin "32") (pinfunction "PC7_32") (pintype "bidirectional"))
      (node (ref "R12") (pin "2") (pinfunction "2_2") (pintype "passive"))
      (node (ref "S1") (pin "3") (pinfunction "2_3") (pintype "passive"))
      (node (ref "U$3") (pin "32") (pinfunction "PC7_32") (pintype "bidirectional"))
    )
    (net (code "22") (name "/SW_D") (class "Default")
      (node (ref "GND") (pin "38") (pinfunction "PF5(ADC5)_38") (pintype "bidirectional"))
      (node (ref "R15") (pin "2") (pinfunction "2_2") (pintype "passive"))
      (node (ref "S4") (pin "3") (pinfunction "2_3") (pintype "passive"))
      (node (ref "U$3") (pin "38") (pinfunction "PF5(ADC5)_38") (pintype "bidirectional"))
    )
    (net (code "23") (name "/SW_E") (class "Default")
      (node (ref "GND") (pin "39") (pinfunction "PF4(ADC4)_39") (pintype "bidirectional"))
      (node (ref "R16") (pin "2") (pinfunction "2_2") (pintype "passive"))
      (node (ref "S5") (pin "3") (pinfunction "2_3") (pintype "passive"))
      (node (ref "U$3") (pin "39") (pinfunction "PF4(ADC4)_39") (pintype "bidirectional"))
    )
    (net (code "24") (name "/TXLED") (class "Default")
      (node (ref "GND") (pin "22") (pinfunction "PD5_22") (pintype "bidirectional"))
      (node (ref "U$3") (pin "22") (pinfunction "PD5_22") (pintype "bidirectional"))
    )
    (net (code "25") (name "/USBVCC") (class "Default")
      (node (ref "F1") (pin "1") (pinfunction "1_1") (pintype "bidirectional"))
      (node (ref "TP10") (pin "P$1") (pinfunction "1_P$1") (pintype "bidirectional"))
      (node (ref "U$1") (pin "PIN$1") (pinfunction "VCC_PIN$1") (pintype "bidirectional"))
    )
    (net (code "26") (name "/VBAT") (class "Default")
      (node (ref "C9") (pin "1") (pinfunction "1_1") (pintype "passive"))
      (node (ref "Q1") (pin "3") (pinfunction "D_3") (pintype "passive"))
      (node (ref "R20") (pin "2") (pinfunction "2_2") (pintype "passive"))
      (node (ref "SJ1") (pin "1") (pinfunction "1_1") (pintype "passive"))
      (node (ref "TP14") (pin "P$1") (pinfunction "1_P$1") (pintype "bidirectional"))
      (node (ref "U3") (pin "3") (pinfunction "VBAT_3") (pintype "power_in"))
    )
    (net (code "27") (name "/VBUS") (class "Default")
      (node (ref "C1") (pin "1") (pinfunction "1_1") (pintype "passive"))
      (node (ref "C12") (pin "1") (pinfunction "1_1") (pintype "passive"))
      (node (ref "C2") (pin "1") (pinfunction "1_1") (pintype "passive"))
      (node (ref "C28") (pin "1") (pinfunction "1_1") (pintype "passive"))
      (node (ref "D2") (pin "C") (pinfunction "C_C") (pintype "passive"))
      (node (ref "GND") (pin "7") (pinfunction "VBUS_7") (pintype "bidirectional"))
      (node (ref "IC2") (pin "5") (pinfunction "VCC_5") (pintype "power_in"))
      (node (ref "Q1") (pin "2") (pinfunction "S_2") (pintype "passive"))
      (node (ref "R6") (pin "1") (pinfunction "1_1") (pintype "passive"))
      (node (ref "R7") (pin "1") (pinfunction "1_1") (pintype "passive"))
      (node (ref "TP12") (pin "P$1") (pinfunction "1_P$1") (pintype "bidirectional"))
      (node (ref "U$3") (pin "7") (pinfunction "VBUS_7") (pintype "bidirectional"))
      (node (ref "U4") (pin "1") (pinfunction "IN_1") (pintype "input"))
    )
    (net (code "28") (name "/VBUS_IN") (class "Default")
      (node (ref "C6") (pin "1") (pinfunction "1_1") (pintype "passive"))
      (node (ref "D2") (pin "A") (pinfunction "A_A") (pintype "passive"))
      (node (ref "F1") (pin "2") (pinfunction "2_2") (pintype "bidirectional"))
      (node (ref "JP16") (pin "1") (pinfunction "1_1") (pintype "passive"))
      (node (ref "JP21") (pin "1") (pinfunction "1_1") (pintype "passive"))
      (node (ref "TP11") (pin "P$1") (pinfunction "1_P$1") (pintype "bidirectional"))
      (node (ref "U2") (pin "3") (pinfunction "VCC_3") (pintype "power_in"))
      (node (ref "U3") (pin "4") (pinfunction "VIN_4") (pintype "power_in"))
    )
    (net (code "29") (name "/XTAL1") (class "Default")
      (node (ref "GND") (pin "17") (pinfunction "XTAL1_17") (pintype "bidirectional"))
      (node (ref "U$3") (pin "17") (pinfunction "XTAL1_17") (pintype "bidirectional"))
      (node (ref "Y1") (pin "1") (pinfunction "1_1") (pintype "passive"))
    )
    (net (code "30") (name "/XTAL2") (class "Default")
      (node (ref "GND") (pin "16") (pinfunction "XTAL2_16") (pintype "bidirectional"))
      (node (ref "U$3") (pin "16") (pinfunction "XTAL2_16") (pintype "bidirectional"))
      (node (ref "Y1") (pin "3") (pinfunction "3_3") (pintype "passive"))
    )
    (net (code "31") (name "3.3V") (class "Default")
      (node (ref "C19") (pin "1") (pinfunction "1_1") (pintype "passive"))
      (node (ref "C21") (pin "2") (pinfunction "2_2") (pintype "passive"))
      (node (ref "C26") (pin "1") (pinfunction "1_1") (pintype "passive"))
      (node (ref "C27") (pin "1") (pinfunction "1_1") (pintype "passive"))
      (node (ref "C32") (pin "1") (pinfunction "1_1") (pintype "passive"))
      (node (ref "C33") (pin "1") (pinfunction "1_1") (pintype "passive"))
      (node (ref "C34") (pin "1") (pinfunction "1_1") (pintype "passive"))
      (node (ref "C5") (pin "1") (pinfunction "1_1") (pintype "passive"))
      (node (ref "GND") (pin "14") (pinfunction "VCC_14") (pintype "bidirectional"))
      (node (ref "GND") (pin "24") (pinfunction "AVCC_24") (pintype "bidirectional"))
      (node (ref "GND") (pin "34") (pinfunction "VCC_34") (pintype "bidirectional"))
      (node (ref "GND") (pin "44") (pinfunction "AVCC_44") (pintype "bidirectional"))
      (node (ref "GND") (pin "6") (pinfunction "UCAP_6") (pintype "bidirectional"))
      (node (ref "J1") (pin "4") (pinfunction "VDD_4") (pintype "bidirectional"))
      (node (ref "JP12") (pin "1") (pinfunction "1_1") (pintype "passive"))
      (node (ref "R11") (pin "1") (pinfunction "1_1") (pintype "passive"))
      (node (ref "R12") (pin "1") (pinfunction "1_1") (pintype "passive"))
      (node (ref "R13") (pin "2") (pinfunction "2_2") (pintype "passive"))
      (node (ref "R14") (pin "2") (pinfunction "2_2") (pintype "passive"))
      (node (ref "R15") (pin "1") (pinfunction "1_1") (pintype "passive"))
      (node (ref "R16") (pin "1") (pinfunction "1_1") (pintype "passive"))
      (node (ref "R4") (pin "2") (pinfunction "2_2") (pintype "passive"))
      (node (ref "R8") (pin "1") (pinfunction "1_1") (pintype "passive"))
      (node (ref "TP13") (pin "P$1") (pinfunction "1_P$1") (pintype "bidirectional"))
      (node (ref "U$3") (pin "14") (pinfunction "VCC_14") (pintype "bidirectional"))
      (node (ref "U$3") (pin "24") (pinfunction "AVCC_24") (pintype "bidirectional"))
      (node (ref "U$3") (pin "34") (pinfunction "VCC_34") (pintype "bidirectional"))
      (node (ref "U$3") (pin "44") (pinfunction "AVCC_44") (pintype "bidirectional"))
      (node (ref "U$3") (pin "6") (pinfunction "UCAP_6") (pintype "bidirectional"))
      (node (ref "U4") (pin "5") (pinfunction "OUT_5") (pintype "passive"))
      (node (ref "X1") (pin "12") (pinfunction "1_12") (pintype "passive"))
      (node (ref "X1") (pin "5") (pinfunction "1_5") (pintype "passive"))
      (node (ref "X2") (pin "12") (pinfunction "1_12") (pintype "passive"))
      (node (ref "X2") (pin "5") (pinfunction "1_5") (pintype "passive"))
    )
    (net (code "32") (name "BATT_STAT") (class "Default")
      (node (ref "GND") (pin "31") (pinfunction "PC6_31") (pintype "bidirectional"))
      (node (ref "R17") (pin "1") (pinfunction "1_1") (pintype "passive"))
      (node (ref "TP3") (pin "P$1") (pinfunction "1_P$1") (pintype "bidirectional"))
      (node (ref "U$3") (pin "31") (pinfunction "PC6_31") (pintype "bidirectional"))
    )
    (net (code "33") (name "GND") (class "Default")
      (node (ref "C1") (pin "2") (pinfunction "2_2") (pintype "passive"))
      (node (ref "C12") (pin "2") (pinfunction "2_2") (pintype "passive"))
      (node (ref "C19") (pin "2") (pinfunction "2_2") (pintype "passive"))
      (node (ref "C2") (pin "2") (pinfunction "2_2") (pintype "passive"))
      (node (ref "C21") (pin "1") (pinfunction "1_1") (pintype "passive"))
      (node (ref "C26") (pin "2") (pinfunction "2_2") (pintype "passive"))
      (node (ref "C27") (pin "2") (pinfunction "2_2") (pintype "passive"))
      (node (ref "C28") (pin "2") (pinfunction "2_2") (pintype "passive"))
      (node (ref "C3") (pin "2") (pinfunction "2_2") (pintype "passive"))
      (node (ref "C32") (pin "2") (pinfunction "2_2") (pintype "passive"))
      (node (ref "C33") (pin "2") (pinfunction "2_2") (pintype "passive"))
      (node (ref "C34") (pin "2") (pinfunction "2_2") (pintype "passive"))
      (node (ref "C36") (pin "1") (pinfunction "1_1") (pintype "passive"))
      (node (ref "C4") (pin "2") (pinfunction "2_2") (pintype "passive"))
      (node (ref "C5") (pin "2") (pinfunction "2_2") (pintype "passive"))
      (node (ref "C6") (pin "2") (pinfunction "2_2") (pintype "passive"))
      (node (ref "C9") (pin "2") (pinfunction "2_2") (pintype "passive"))
      (node (ref "GND") (pin "15") (pinfunction "GND_15") (pintype "bidirectional"))
      (node (ref "GND") (pin "23") (pinfunction "GND_23") (pintype "bidirectional"))
      (node (ref "GND") (pin "33") (pinfunction "PE2/~{HWB}_33") (pintype "bidirectional"))
      (node (ref "GND") (pin "35") (pinfunction "GND_35") (pintype "bidirectional"))
      (node (ref "GND") (pin "43") (pinfunction "GND_43") (pintype "bidirectional"))
      (node (ref "GND") (pin "5") (pinfunction "UGND_5") (pintype "bidirectional"))
      (node (ref "GND") (pin "P$1") (pinfunction "GND_PAD_P$1") (pintype "bidirectional"))
      (node (ref "IC2") (pin "3") (pinfunction "GND_3") (pintype "power_in"))
      (node (ref "J1") (pin "6") (pinfunction "VSS_6") (pintype "bidirectional"))
      (node (ref "J1") (pin "G1") (pinfunction "G1_G1") (pintype "bidirectional"))
      (node (ref "J1") (pin "G2") (pinfunction "G2_G2") (pintype "bidirectional"))
      (node (ref "J1") (pin "G3") (pinfunction "G3_G3") (pintype "bidirectional"))
      (node (ref "J1") (pin "G4") (pinfunction "G4_G4") (pintype "bidirectional"))
      (node (ref "JP1") (pin "1") (pinfunction "1_1") (pintype "passive"))
      (node (ref "JP11") (pin "1") (pinfunction "1_1") (pintype "passive"))
      (node (ref "R3") (pin "2") (pinfunction "2_2") (pintype "passive"))
      (node (ref "S1") (pin "1") (pinfunction "1_1") (pintype "passive"))
      (node (ref "S2") (pin "1") (pinfunction "1_1") (pintype "passive"))
      (node (ref "S3") (pin "1") (pinfunction "1_1") (pintype "passive"))
      (node (ref "S4") (pin "1") (pinfunction "1_1") (pintype "passive"))
      (node (ref "S5") (pin "1") (pinfunction "1_1") (pintype "passive"))
      (node (ref "S6") (pin "3") (pinfunction "2_3") (pintype "passive"))
      (node (ref "TP15") (pin "P$1") (pinfunction "1_P$1") (pintype "bidirectional"))
      (node (ref "U$1") (pin "PAD$1") (pinfunction "SHIELD_PAD$1") (pintype "bidirectional"))
      (node (ref "U$1") (pin "PAD$10") (pinfunction "SHIELD_PAD$10") (pintype "bidirectional"))
      (node (ref "U$1") (pin "PAD$2") (pinfunction "SHIELD_PAD$2") (pintype "bidirectional"))
      (node (ref "U$1") (pin "PAD$3") (pinfunction "SHIELD_PAD$3") (pintype "bidirectional"))
      (node (ref "U$1") (pin "PAD$4") (pinfunction "SHIELD_PAD$4") (pintype "bidirectional"))
      (node (ref "U$1") (pin "PAD$5") (pinfunction "SHIELD_PAD$5") (pintype "bidirectional"))
      (node (ref "U$1") (pin "PAD$6") (pinfunction "SHIELD_PAD$6") (pintype "bidirectional"))
      (node (ref "U$1") (pin "PAD$7") (pinfunction "SHIELD_PAD$7") (pintype "bidirectional"))
      (node (ref "U$1") (pin "PAD$8") (pinfunction "SHIELD_PAD$8") (pintype "bidirectional"))
      (node (ref "U$1") (pin "PAD$9") (pinfunction "SHIELD_PAD$9") (pintype "bidirectional"))
      (node (ref "U$1") (pin "PIN$5") (pinfunction "GND_PIN$5") (pintype "bidirectional"))
      (node (ref "U$2") (pin "P$3") (pinfunction "GND_P$3") (pintype "bidirectional"))
      (node (ref "U$2") (pin "P$4") (pinfunction "P$4_P$4") (pintype "bidirectional"))
      (node (ref "U$2") (pin "P$5") (pinfunction "P$5_P$5") (pintype "bidirectional"))
      (node (ref "U$3") (pin "15") (pinfunction "GND_15") (pintype "bidirectional"))
      (node (ref "U$3") (pin "23") (pinfunction "GND_23") (pintype "bidirectional"))
      (node (ref "U$3") (pin "33") (pinfunction "PE2/~{HWB}_33") (pintype "bidirectional"))
      (node (ref "U$3") (pin "35") (pinfunction "GND_35") (pintype "bidirectional"))
      (node (ref "U$3") (pin "43") (pinfunction "GND_43") (pintype "bidirectional"))
      (node (ref "U$3") (pin "5") (pinfunction "UGND_5") (pintype "bidirectional"))
      (node (ref "U2") (pin "1") (pinfunction "GND_1") (pintype "power_in"))
      (node (ref "U3") (pin "2") (pinfunction "VSS_2") (pintype "power_in"))
      (node (ref "U4") (pin "2") (pinfunction "GND_2") (pintype "input"))
      (node (ref "X1") (pin "4") (pinfunction "1_4") (pintype "passive"))
      (node (ref "X2") (pin "4") (pinfunction "1_4") (pintype "passive"))
      (node (ref "Y1") (pin "2") (pinfunction "2_2") (pintype "passive"))
      (node (ref "Z1") (pin "1") (pinfunction "1_1") (pintype "passive"))
      (node (ref "Z2") (pin "1") (pinfunction "1_1") (pintype "passive"))
    )
    (net (code "34") (name "Net-(C36-Pad2)") (class "Default")
      (node (ref "C36") (pin "2") (pinfunction "2_2") (pintype "passive"))
      (node (ref "X1") (pin "1") (pinfunction "1_1") (pintype "passive"))
      (node (ref "X2") (pin "1") (pinfunction "1_1") (pintype "passive"))
    )
    (net (code "35") (name "Net-(GND-AREF)") (class "Default")
      (node (ref "C3") (pin "1") (pinfunction "1_1") (pintype "passive"))
      (node (ref "GND") (pin "42") (pinfunction "AREF_42") (pintype "bidirectional"))
      (node (ref "U$3") (pin "42") (pinfunction "AREF_42") (pintype "bidirectional"))
    )
    (net (code "36") (name "Net-(GND-UVCC)") (class "Default")
      (node (ref "GND") (pin "2") (pinfunction "UVCC_2") (pintype "bidirectional"))
      (node (ref "U$3") (pin "2") (pinfunction "UVCC_2") (pintype "bidirectional"))
    )
    (net (code "37") (name "Net-(Q1-G)") (class "Default")
      (node (ref "Q1") (pin "1") (pinfunction "G_1") (pintype "passive"))
      (node (ref "U2") (pin "2") (pinfunction "~{RST}_2") (pintype "bidirectional"))
    )
    (net (code "38") (name "Net-(U$1-D+)") (class "Default")
      (node (ref "R9") (pin "1") (pinfunction "1_1") (pintype "passive"))
      (node (ref "U$1") (pin "PIN$3") (pinfunction "D+_PIN$3") (pintype "bidirectional"))
      (node (ref "Z1") (pin "2") (pinfunction "2_2") (pintype "passive"))
    )
    (net (code "39") (name "Net-(U$1-D-)") (class "Default")
      (node (ref "R10") (pin "1") (pinfunction "1_1") (pintype "passive"))
      (node (ref "U$1") (pin "PIN$2") (pinfunction "D-_PIN$2") (pintype "bidirectional"))
      (node (ref "Z2") (pin "2") (pinfunction "2_2") (pintype "passive"))
    )
    (net (code "40") (name "Net-(U$2-VBAT)") (class "Default")
      (node (ref "SJ1") (pin "2") (pinfunction "2_2") (pintype "passive"))
      (node (ref "U$2") (pin "P$1") (pinfunction "VBAT_P$1") (pintype "bidirectional"))
    )
    (net (code "41") (name "Net-(U3-PROG)") (class "Default")
      (node (ref "R3") (pin "1") (pinfunction "1_1") (pintype "passive"))
      (node (ref "U3") (pin "5") (pinfunction "PROG_5") (pintype "input"))
    )
    (net (code "42") (name "Net-(U3-STAT)") (class "Default")
      (node (ref "R17") (pin "2") (pinfunction "2_2") (pintype "passive"))
      (node (ref "U3") (pin "1") (pinfunction "STAT_1") (pintype "output"))
    )
    (net (code "43") (name "Net-(U4-BP)") (class "Default")
      (node (ref "C4") (pin "1") (pinfunction "1_1") (pintype "passive"))
      (node (ref "U4") (pin "4") (pinfunction "BP_4") (pintype "input"))
    )
    (net (code "44") (name "Net-(X1C-1)") (class "Default")
      (node (ref "R19") (pin "1") (pinfunction "1_1") (pintype "passive"))
      (node (ref "X1") (pin "11") (pinfunction "1_11") (pintype "passive"))
      (node (ref "X2") (pin "11") (pinfunction "1_11") (pintype "passive"))
    )
    (net (code "45") (name "Net-(X1E-1)") (class "Default")
      (node (ref "C35") (pin "2") (pinfunction "2_2") (pintype "passive"))
      (node (ref "X1") (pin "2") (pinfunction "1_2") (pintype "passive"))
      (node (ref "X2") (pin "2") (pinfunction "1_2") (pintype "passive"))
    )
    (net (code "46") (name "Net-(X1F-1)") (class "Default")
      (node (ref "C35") (pin "1") (pinfunction "1_1") (pintype "passive"))
      (node (ref "X1") (pin "3") (pinfunction "1_3") (pintype "passive"))
      (node (ref "X2") (pin "3") (pinfunction "1_3") (pintype "passive"))
    )
    (net (code "47") (name "PWR_ONOFF") (class "Default")
      (node (ref "GND") (pin "41") (pinfunction "PF0(ADC0)_41") (pintype "bidirectional"))
      (node (ref "IC2") (pin "1") (pinfunction "A_1") (pintype "input"))
      (node (ref "JP1") (pin "2") (pinfunction "2_2") (pintype "passive"))
      (node (ref "R7") (pin "2") (pinfunction "2_2") (pintype "passive"))
      (node (ref "TP9") (pin "P$1") (pinfunction "1_P$1") (pintype "bidirectional"))
      (node (ref "U$3") (pin "41") (pinfunction "PF0(ADC0)_41") (pintype "bidirectional"))
    )
    (net (code "48") (name "SW_PWR") (class "Default")
      (node (ref "GND") (pin "40") (pinfunction "PF1(ADC1)_40") (pintype "bidirectional"))
      (node (ref "IC2") (pin "2") (pinfunction "B_2") (pintype "input"))
      (node (ref "R6") (pin "2") (pinfunction "2_2") (pintype "passive"))
      (node (ref "S6") (pin "1") (pinfunction "1_1") (pintype "passive"))
      (node (ref "TP1") (pin "P$1") (pinfunction "1_P$1") (pintype "bidirectional"))
      (node (ref "U$3") (pin "40") (pinfunction "PF1(ADC1)_40") (pintype "bidirectional"))
    )
    (net (code "49") (name "VBAT_EN") (class "Default")
      (node (ref "GND") (pin "30") (pinfunction "PB6(ADC13)_30") (pintype "bidirectional"))
      (node (ref "R24") (pin "2") (pinfunction "2_2") (pintype "passive"))
      (node (ref "U$3") (pin "30") (pinfunction "PB6(ADC13)_30") (pintype "bidirectional"))
    )
    (net (code "50") (name "VBAT_SENSE") (class "Default")
      (node (ref "GND") (pin "29") (pinfunction "PB5(ADC12)_29") (pintype "bidirectional"))
      (node (ref "R20") (pin "1") (pinfunction "1_1") (pintype "passive"))
      (node (ref "R24") (pin "1") (pinfunction "1_1") (pintype "passive"))
      (node (ref "TP4") (pin "P$1") (pinfunction "1_P$1") (pintype "bidirectional"))
      (node (ref "U$3") (pin "29") (pinfunction "PB5(ADC12)_29") (pintype "bidirectional"))
    )
    (net (code "51") (name "unconnected-(J1-CDN-Pad9)") (class "Default")
      (node (ref "J1") (pin "9") (pinfunction "CDN_9") (pintype "bidirectional"))
    )
    (net (code "52") (name "unconnected-(J1-DATA1-Pad8)") (class "Default")
      (node (ref "J1") (pin "8") (pinfunction "DATA1_8") (pintype "bidirectional"))
    )
    (net (code "53") (name "unconnected-(J1-DATA2-Pad1)") (class "Default")
      (node (ref "J1") (pin "1") (pinfunction "DATA2_1") (pintype "bidirectional"))
    )
    (net (code "54") (name "unconnected-(JP23-Pad1)") (class "Default")
      (node (ref "JP23") (pin "1") (pinfunction "1_1") (pintype "passive"))
    )
    (net (code "55") (name "unconnected-(JP24-Pad1)") (class "Default")
      (node (ref "JP24") (pin "1") (pinfunction "1_1") (pintype "passive"))
    )
    (net (code "56") (name "unconnected-(JP25-Pad1)") (class "Default")
      (node (ref "JP25") (pin "1") (pinfunction "1_1") (pintype "passive"))
    )
    (net (code "57") (name "unconnected-(U$1-ID-PadPIN$4)") (class "Default")
      (node (ref "U$1") (pin "PIN$4") (pinfunction "ID_PIN$4") (pintype "bidirectional"))
    )
    (net (code "58") (name "unconnected-(U$2-BSI-PadP$2)") (class "Default")
      (node (ref "U$2") (pin "P$2") (pinfunction "BSI_P$2") (pintype "bidirectional"))
    )
  )
)
